# module.net
KiCad netlist of a schematic drawn in EAGLE
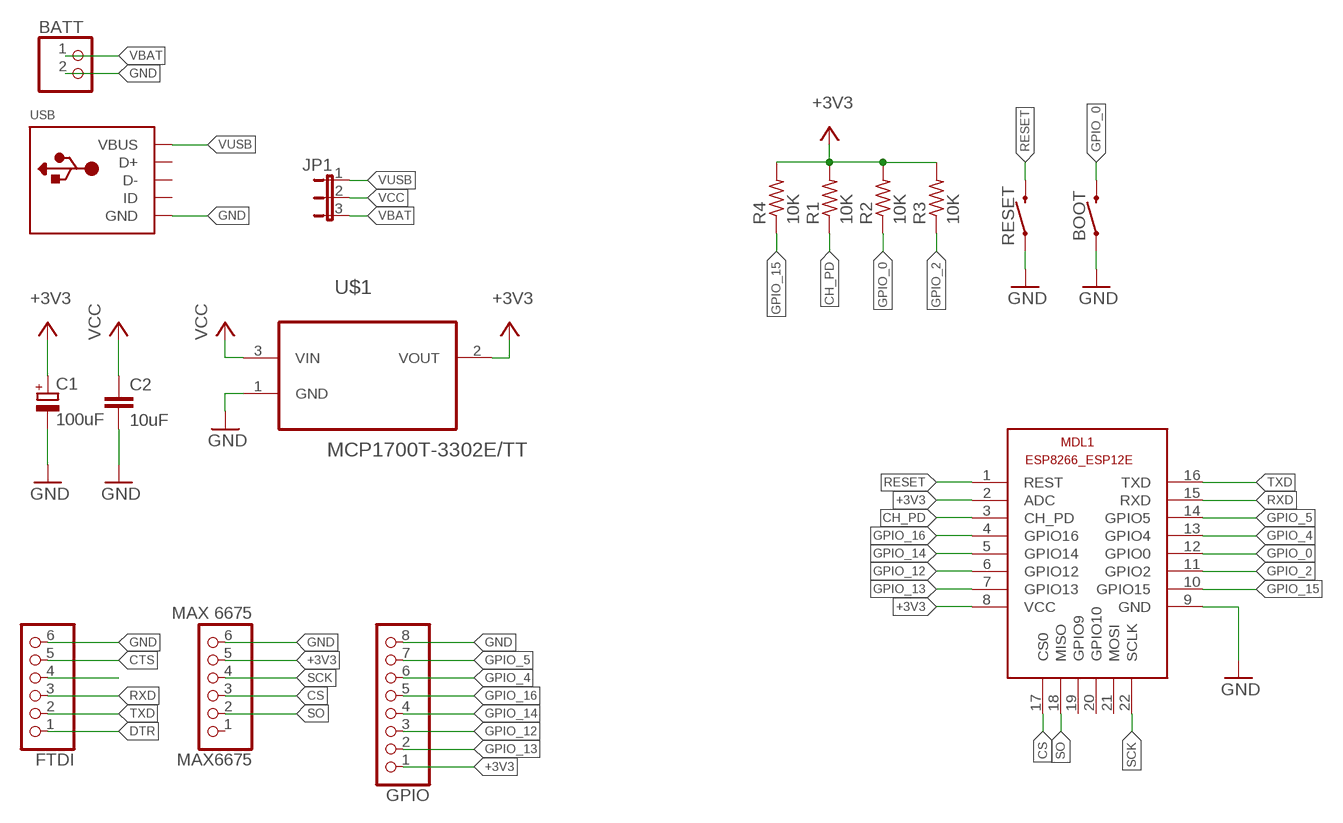
[diagram p0: schematic, sheet 1]

(export (version "E")
  (design (tool "Eeschema 10.0.6"))
  (components
    (comp (ref "BATT")
      (value "PINHD-1X2")
      (footprint "eagle-import:1X02")
      (libsource (lib "eagle-import") (part "PINHD-1X2"))
    )
    (comp (ref "BOOT")
      (value "gpio0")
      (footprint "eagle-import:TACTILE_SWITCH_SMD_4.5MM")
      (libsource (lib "eagle-import") (part "MOMENTARY-SWITCH-SPST-SMD-4.5MM"))
    )
    (comp (ref "C1")
      (value "100uF")
      (footprint "eagle-import:085CS_1AR")
      (libsource (lib "eagle-import") (part "CPOL-EU085CS-1AR"))
    )
    (comp (ref "C2")
      (value "10uF")
      (footprint "eagle-import:C1206K")
      (libsource (lib "eagle-import") (part "C-EUC1206K"))
    )
    (comp (ref "FTDI")
      (value "PINHD-1X6B")
      (footprint "eagle-import:1X06-BIG")
      (libsource (lib "eagle-import") (part "PINHD-1X6B"))
    )
    (comp (ref "GPIO")
      (value "PINHD-1X8BIG")
      (footprint "eagle-import:1X08-BIG")
      (libsource (lib "eagle-import") (part "PINHD-1X8BIG"))
    )
    (comp (ref "JP1")
      (value "JP2E")
      (footprint "eagle-import:JP2")
      (libsource (lib "eagle-import") (part "JP2E"))
    )
    (comp (ref "MAX6675")
      (value "MAX 6675")
      (footprint "eagle-import:1X06-BIG")
      (libsource (lib "eagle-import") (part "PINHD-1X6B"))
    )
    (comp (ref "MDL1")
      (value "ESP8266-12EESP8266-ESP12E")
      (footprint "eagle-import:ESP8266-ESP12E")
      (libsource (lib "eagle-import") (part "ESP8266-12EESP8266-ESP12E"))
    )
    (comp (ref "R1")
      (value "10K")
      (footprint "eagle-import:M0805")
      (libsource (lib "eagle-import") (part "R-US_M0805"))
    )
    (comp (ref "R2")
      (value "10K")
      (footprint "eagle-import:M0805")
      (libsource (lib "eagle-import") (part "R-US_M0805"))
    )
    (comp (ref "R3")
      (value "10K")
      (footprint "eagle-import:M0805")
      (libsource (lib "eagle-import") (part "R-US_M0805"))
    )
    (comp (ref "R4")
      (value "10K")
      (footprint "eagle-import:M0805")
      (libsource (lib "eagle-import") (part "R-US_M0805"))
    )
    (comp (ref "RESET")
      (value "reset")
      (footprint "eagle-import:TACTILE_SWITCH_SMD_4.5MM")
      (libsource (lib "eagle-import") (part "MOMENTARY-SWITCH-SPST-SMD-4.5MM"))
    )
    (comp (ref "U$1")
      (value "MCP1700T-3302E/TT")
      (footprint "eagle-import:SOT95P237X112-3N")
      (fields (field (name "MF") "Microchip"))
      (libsource (lib "eagle-import") (part "MCP1700T-3302E/TT"))
    )
    (comp (ref "USB")
      (value "USBMICRO_20329")
      (footprint "eagle-import:4UCONN_20329")
      (libsource (lib "eagle-import") (part "USBMICRO_20329"))
    )
  )
  (nets
    (net (code "1") (name "+3V3") (class "Default")
      (node (ref "C1") (pin "+") (pinfunction "+_+") (pintype "passive"))
      (node (ref "GPIO") (pin "1") (pinfunction "1_1") (pintype "passive"))
      (node (ref "MAX6675") (pin "5") (pinfunction "5_5") (pintype "passive"))
      (node (ref "MDL1") (pin "2") (pinfunction "ADC_2") (pintype "bidirectional"))
      (node (ref "MDL1") (pin "8") (pinfunction "VCC_8") (pintype "bidirectional"))
      (node (ref "R1") (pin "2") (pinfunction "2_2") (pintype "passive"))
      (node (ref "R2") (pin "2") (pinfunction "2_2") (pintype "passive"))
      (node (ref "R3") (pin "2") (pinfunction "2_2") (pintype "passive"))
      (node (ref "R4") (pin "2") (pinfunction "2_2") (pintype "passive"))
      (node (ref "U$1") (pin "2") (pinfunction "VOUT_2") (pintype "output"))
    )
    (net (code "2") (name "CH_PD") (class "Default")
      (node (ref "MDL1") (pin "3") (pinfunction "CH_PD_3") (pintype "bidirectional"))
      (node (ref "R1") (pin "1") (pinfunction "1_1") (pintype "passive"))
    )
    (net (code "3") (name "CS") (class "Default")
      (node (ref "MAX6675") (pin "3") (pinfunction "3_3") (pintype "passive"))
      (node (ref "MDL1") (pin "17") (pinfunction "CS0_17") (pintype "bidirectional"))
    )
    (net (code "4") (name "CTS") (class "Default")
      (node (ref "FTDI") (pin "5") (pinfunction "5_5") (pintype "passive"))
    )
    (net (code "5") (name "DTR") (class "Default")
      (node (ref "FTDI") (pin "1") (pinfunction "1_1") (pintype "passive"))
    )
    (net (code "6") (name "GND") (class "Default")
      (node (ref "BATT") (pin "2") (pinfunction "2_2") (pintype "passive"))
      (node (ref "BOOT") (pin "2") (pinfunction "1_2") (pintype "passive"))
      (node (ref "BOOT") (pin "3") (pinfunction "1_3") (pintype "passive"))
      (node (ref "C1") (pin "-") (pinfunction "-_-") (pintype "passive"))
      (node (ref "C2") (pin "2") (pinfunction "2_2") (pintype "passive"))
      (node (ref "FTDI") (pin "6") (pinfunction "6_6") (pintype "passive"))
      (node (ref "GPIO") (pin "8") (pinfunction "8_8") (pintype "passive"))
      (node (ref "MAX6675") (pin "6") (pinfunction "6_6") (pintype "passive"))
      (node (ref "MDL1") (pin "9") (pinfunction "GND_9") (pintype "bidirectional"))
      (node (ref "RESET") (pin "2") (pinfunction "1_2") (pintype "passive"))
      (node (ref "RESET") (pin "3") (pinfunction "1_3") (pintype "passive"))
      (node (ref "U$1") (pin "1") (pinfunction "GND_1") (pintype "passive"))
      (node (ref "USB") (pin "BASE@1") (pinfunction "GND_BASE@1") (pintype "power_in"))
      (node (ref "USB") (pin "BASE@2") (pinfunction "GND_BASE@2") (pintype "power_in"))
      (node (ref "USB") (pin "GND") (pinfunction "GND_GND") (pintype "power_in"))
      (node (ref "USB") (pin "SPRT@1") (pinfunction "GND_SPRT@1") (pintype "power_in"))
      (node (ref "USB") (pin "SPRT@2") (pinfunction "GND_SPRT@2") (pintype "power_in"))
      (node (ref "USB") (pin "SPRT@3") (pinfunction "GND_SPRT@3") (pintype "power_in"))
      (node (ref "USB") (pin "SPRT@4") (pinfunction "GND_SPRT@4") (pintype "power_in"))
    )
    (net (code "7") (name "GPIO_0") (class "Default")
      (node (ref "BOOT") (pin "1") (pinfunction "2_1") (pintype "passive"))
      (node (ref "BOOT") (pin "4") (pinfunction "2_4") (pintype "passive"))
      (node (ref "MDL1") (pin "12") (pinfunction "GPIO0_12") (pintype "bidirectional"))
      (node (ref "R2") (pin "1") (pinfunction "1_1") (pintype "passive"))
    )
    (net (code "8") (name "GPIO_2") (class "Default")
      (node (ref "MDL1") (pin "11") (pinfunction "GPIO2_11") (pintype "bidirectional"))
      (node (ref "R3") (pin "1") (pinfunction "1_1") (pintype "passive"))
    )
    (net (code "9") (name "GPIO_4") (class "Default")
      (node (ref "GPIO") (pin "6") (pinfunction "6_6") (pintype "passive"))
      (node (ref "MDL1") (pin "13") (pinfunction "GPIO4_13") (pintype "bidirectional"))
    )
    (net (code "10") (name "GPIO_5") (class "Default")
      (node (ref "GPIO") (pin "7") (pinfunction "7_7") (pintype "passive"))
      (node (ref "MDL1") (pin "14") (pinfunction "GPIO5_14") (pintype "bidirectional"))
    )
    (net (code "11") (name "GPIO_12") (class "Default")
      (node (ref "GPIO") (pin "3") (pinfunction "3_3") (pintype "passive"))
      (node (ref "MDL1") (pin "6") (pinfunction "GPIO12_6") (pintype "bidirectional"))
    )
    (net (code "12") (name "GPIO_13") (class "Default")
      (node (ref "GPIO") (pin "2") (pinfunction "2_2") (pintype "passive"))
      (node (ref "MDL1") (pin "7") (pinfunction "GPIO13_7") (pintype "bidirectional"))
    )
    (net (code "13") (name "GPIO_14") (class "Default")
      (node (ref "GPIO") (pin "4") (pinfunction "4_4") (pintype "passive"))
      (node (ref "MDL1") (pin "5") (pinfunction "GPIO14_5") (pintype "bidirectional"))
    )
    (net (code "14") (name "GPIO_15") (class "Default")
      (node (ref "MDL1") (pin "10") (pinfunction "GPIO15_10") (pintype "bidirectional"))
      (node (ref "R4") (pin "1") (pinfunction "1_1") (pintype "passive"))
    )
    (net (code "15") (name "GPIO_16") (class "Default")
      (node (ref "GPIO") (pin "5") (pinfunction "5_5") (pintype "passive"))
      (node (ref "MDL1") (pin "4") (pinfunction "GPIO16_4") (pintype "bidirectional"))
    )
    (net (code "16") (name "RESET") (class "Default")
      (node (ref "MDL1") (pin "1") (pinfunction "REST_1") (pintype "bidirectional"))
      (node (ref "RESET") (pin "1") (pinfunction "2_1") (pintype "passive"))
      (node (ref "RESET") (pin "4") (pinfunction "2_4") (pintype "passive"))
    )
    (net (code "17") (name "RXD") (class "Default")
      (node (ref "FTDI") (pin "3") (pinfunction "3_3") (pintype "passive"))
      (node (ref "MDL1") (pin "15") (pinfunction "RXD_15") (pintype "bidirectional"))
    )
    (net (code "18") (name "SCK") (class "Default")
      (node (ref "MAX6675") (pin "4") (pinfunction "4_4") (pintype "passive"))
      (node (ref "MDL1") (pin "22") (pinfunction "SCLK_22") (pintype "bidirectional"))
    )
    (net (code "19") (name "SO") (class "Default")
      (node (ref "MAX6675") (pin "2") (pinfunction "2_2") (pintype "passive"))
      (node (ref "MDL1") (pin "18") (pinfunction "MISO_18") (pintype "bidirectional"))
    )
    (net (code "20") (name "TXD") (class "Default")
      (node (ref "FTDI") (pin "2") (pinfunction "2_2") (pintype "passive"))
      (node (ref "MDL1") (pin "16") (pinfunction "TXD_16") (pintype "bidirectional"))
    )
    (net (code "21") (name "VBAT") (class "Default")
      (node (ref "BATT") (pin "1") (pinfunction "1_1") (pintype "passive"))
      (node (ref "JP1") (pin "3") (pinfunction "3_3") (pintype "passive"))
    )
    (net (code "22") (name "VCC") (class "Default")
      (node (ref "C2") (pin "1") (pinfunction "1_1") (pintype "passive"))
      (node (ref "JP1") (pin "2") (pinfunction "2_2") (pintype "passive"))
      (node (ref "U$1") (pin "3") (pinfunction "VIN_3") (pintype "input"))
    )
    (net (code "23") (name "VUSB") (class "Default")
      (node (ref "JP1") (pin "1") (pinfunction "1_1") (pintype "passive"))
      (node (ref "USB") (pin "VBUS") (pinfunction "VBUS_VBUS") (pintype "power_in"))
    )
    (net (code "24") (name "unconnected-(FTDI-Pad4)") (class "Default")
      (node (ref "FTDI") (pin "4") (pinfunction "4_4") (pintype "passive"))
    )
    (net (code "25") (name "unconnected-(MAX6675-Pad1)") (class "Default")
      (node (ref "MAX6675") (pin "1") (pinfunction "1_1") (pintype "passive"))
    )
    (net (code "26") (name "unconnected-(MDL1-GPIO9-Pad19)") (class "Default")
      (node (ref "MDL1") (pin "19") (pinfunction "GPIO9_19") (pintype "bidirectional"))
    )
    (net (code "27") (name "unconnected-(MDL1-GPIO10-Pad20)") (class "Default")
      (node (ref "MDL1") (pin "20") (pinfunction "GPIO10_20") (pintype "bidirectional"))
    )
    (net (code "28") (name "unconnected-(MDL1-MOSI-Pad21)") (class "Default")
      (node (ref "MDL1") (pin "21") (pinfunction "MOSI_21") (pintype "bidirectional"))
    )
    (net (code "29") (name "unconnected-(USB-PadD+)") (class "Default")
      (node (ref "USB") (pin "D+") (pinfunction "D+_D+") (pintype "bidirectional"))
    )
    (net (code "30") (name "unconnected-(USB-PadD-)") (class "Default")
      (node (ref "USB") (pin "D-") (pinfunction "D-_D-") (pintype "bidirectional"))
    )
    (net (code "31") (name "unconnected-(USB-PadID)") (class "Default")
      (node (ref "USB") (pin "ID") (pinfunction "ID_ID") (pintype "bidirectional"))
    )
  )
)
